# GaggiaBabyClassWiring.net
KiCad netlist of a schematic drawn in EAGLE
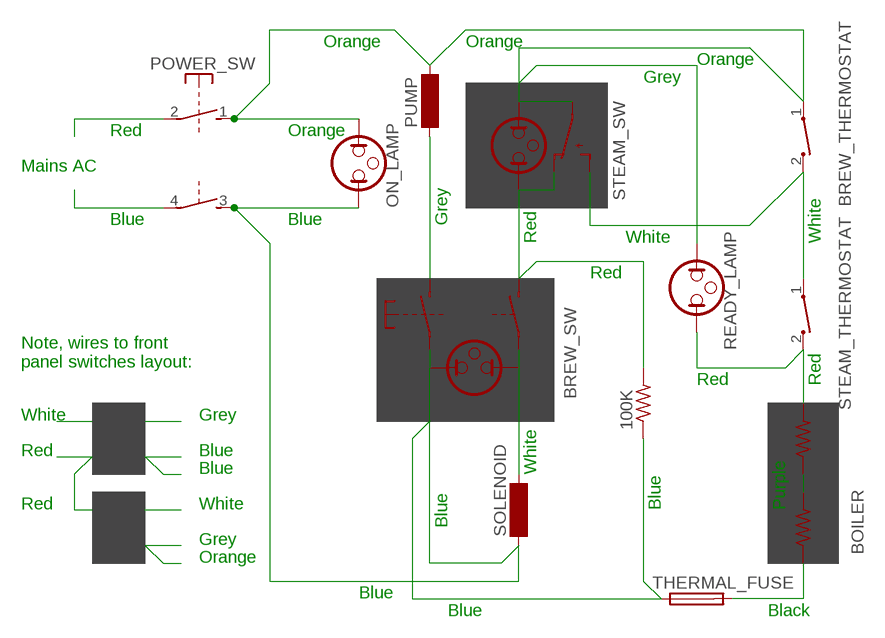
[diagram p0: schematic, sheet 1]

(export (version "E")
  (design (tool "Eeschema 10.0.6"))
  (components
    (comp (ref "100K")
      (value "R-US_0204/2V")
      (footprint "eagle-import:0204V")
      (libsource (lib "eagle-import") (part "R-US_0204/2V"))
    )
    (comp (ref "100K2")
      (value "R-US_0204/2V")
      (footprint "eagle-import:0204V")
      (libsource (lib "eagle-import") (part "R-US_0204/2V"))
    )
    (comp (ref "BOILER")
      (value "R-US_0204/2V")
      (footprint "eagle-import:0204V")
      (libsource (lib "eagle-import") (part "R-US_0204/2V"))
    )
    (comp (ref "BREW_SW")
      (value "PVA1")
      (footprint "eagle-import:PVA1F")
      (libsource (lib "eagle-import") (part "PVA1"))
    )
    (comp (ref "BREW_THERMOSTAT")
      (value "CT10-XXXX-A2")
      (footprint "eagle-import:CT10-XXXX-A2")
      (libsource (lib "eagle-import") (part "CT10-XXXX-A2"))
    )
    (comp (ref "BR_LMP")
      (value "NEON")
      (footprint "eagle-import:LDH-3R")
      (libsource (lib "eagle-import") (part "NEON"))
    )
    (comp (ref "ON_LAMP")
      (value "NEON")
      (footprint "eagle-import:LDH-3R")
      (libsource (lib "eagle-import") (part "NEON"))
    )
    (comp (ref "POWER_SW")
      (value "PVA1")
      (footprint "eagle-import:PVA1F")
      (libsource (lib "eagle-import") (part "PVA1"))
    )
    (comp (ref "PUMP")
      (value "SM-L15A")
      (footprint "eagle-import:SM-L15A")
      (libsource (lib "eagle-import") (part "SM-L15A"))
    )
    (comp (ref "READY_LAMP")
      (value "NEON")
      (footprint "eagle-import:LDH-3R")
      (libsource (lib "eagle-import") (part "NEON"))
    )
    (comp (ref "SOLENOID")
      (value "SM-L15A")
      (footprint "eagle-import:SM-L15A")
      (libsource (lib "eagle-import") (part "SM-L15A"))
    )
    (comp (ref "STEAM_SW")
      (value "TL32PO")
      (footprint "eagle-import:TL3XPO")
      (libsource (lib "eagle-import") (part "TL32PO"))
    )
    (comp (ref "STEAM_THERMOSTAT")
      (value "CT10-XXXX-A2")
      (footprint "eagle-import:CT10-XXXX-A2")
      (libsource (lib "eagle-import") (part "CT10-XXXX-A2"))
    )
    (comp (ref "ST_LMP")
      (value "NEON")
      (footprint "eagle-import:LDH-3R")
      (libsource (lib "eagle-import") (part "NEON"))
    )
    (comp (ref "THERMAL_FUSE")
      (value "19559")
      (footprint "eagle-import:19559")
      (fields (field (name "MPN") "55900000001"))
      (libsource (lib "eagle-import") (part "19559"))
    )
  )
  (nets
    (net (code "1") (name "Net-(100K2-Pad1)") (class "Default")
      (node (ref "100K2") (pin "1") (pinfunction "1_1") (pintype "passive"))
      (node (ref "BOILER") (pin "2") (pinfunction "2_2") (pintype "passive"))
    )
    (net (code "2") (name "Net-(100K2-Pad2)") (class "Default")
      (node (ref "100K2") (pin "2") (pinfunction "2_2") (pintype "passive"))
      (node (ref "READY_LAMP") (pin "1") (pinfunction "1_1") (pintype "passive"))
      (node (ref "STEAM_THERMOSTAT") (pin "2") (pinfunction "2_2") (pintype "passive"))
    )
    (net (code "3") (name "Net-(BOILER-Pad1)") (class "Default")
      (node (ref "BOILER") (pin "1") (pinfunction "1_1") (pintype "passive"))
      (node (ref "THERMAL_FUSE") (pin "2") (pinfunction "2_2") (pintype "passive"))
    )
    (net (code "4") (name "Net-(BREW_SWA-P)") (class "Default")
      (node (ref "100K") (pin "1") (pinfunction "1_1") (pintype "passive"))
      (node (ref "BREW_SW") (pin "2") (pinfunction "P_2") (pintype "passive"))
      (node (ref "BR_LMP") (pin "2") (pinfunction "2_2") (pintype "passive"))
      (node (ref "ON_LAMP") (pin "1") (pinfunction "1_1") (pintype "passive"))
      (node (ref "POWER_SW") (pin "3") (pinfunction "S_3") (pintype "passive"))
      (node (ref "SOLENOID") (pin "1") (pinfunction "1_1") (pintype "passive"))
      (node (ref "THERMAL_FUSE") (pin "1") (pinfunction "1_1") (pintype "passive"))
    )
    (net (code "5") (name "Net-(BREW_SWA-S)") (class "Default")
      (node (ref "BREW_SW") (pin "1") (pinfunction "S_1") (pintype "passive"))
      (node (ref "PUMP") (pin "1") (pinfunction "1_1") (pintype "passive"))
    )
    (net (code "6") (name "Net-(BREW_SWB-P)") (class "Default")
      (node (ref "BREW_SW") (pin "4") (pinfunction "P_4") (pintype "passive"))
      (node (ref "BR_LMP") (pin "1") (pinfunction "1_1") (pintype "passive"))
      (node (ref "SOLENOID") (pin "2") (pinfunction "2_2") (pintype "passive"))
    )
    (net (code "7") (name "Net-(BREW_SWB-S)") (class "Default")
      (node (ref "100K") (pin "2") (pinfunction "2_2") (pintype "passive"))
      (node (ref "BREW_SW") (pin "3") (pinfunction "S_3") (pintype "passive"))
      (node (ref "STEAM_SW") (pin "1") (pinfunction "O_1") (pintype "passive"))
      (node (ref "ST_LMP") (pin "1") (pinfunction "1_1") (pintype "passive"))
    )
    (net (code "8") (name "Net-(POWER_SWA-S)") (class "Default")
      (node (ref "BREW_THERMOSTAT") (pin "1") (pinfunction "1_1") (pintype "passive"))
      (node (ref "ON_LAMP") (pin "2") (pinfunction "2_2") (pintype "passive"))
      (node (ref "POWER_SW") (pin "1") (pinfunction "S_1") (pintype "passive"))
      (node (ref "PUMP") (pin "2") (pinfunction "2_2") (pintype "passive"))
      (node (ref "READY_LAMP") (pin "2") (pinfunction "2_2") (pintype "passive"))
      (node (ref "STEAM_SW") (pin "2") (pinfunction "P_2") (pintype "passive"))
      (node (ref "ST_LMP") (pin "2") (pinfunction "2_2") (pintype "passive"))
    )
    (net (code "9") (name "Net-(STEAM_SW-S)") (class "Default")
      (node (ref "BREW_THERMOSTAT") (pin "2") (pinfunction "2_2") (pintype "passive"))
      (node (ref "STEAM_SW") (pin "3") (pinfunction "S_3") (pintype "passive"))
      (node (ref "STEAM_THERMOSTAT") (pin "1") (pinfunction "1_1") (pintype "passive"))
    )
    (net (code "10") (name "unconnected-(POWER_SWA-P-Pad2)") (class "Default")
      (node (ref "POWER_SW") (pin "2") (pinfunction "P_2") (pintype "passive"))
    )
    (net (code "11") (name "unconnected-(POWER_SWB-P-Pad4)") (class "Default")
      (node (ref "POWER_SW") (pin "4") (pinfunction "P_4") (pintype "passive"))
    )
  )
)
